# Pwr.net
KiCad netlist of a schematic drawn in Altium Designer
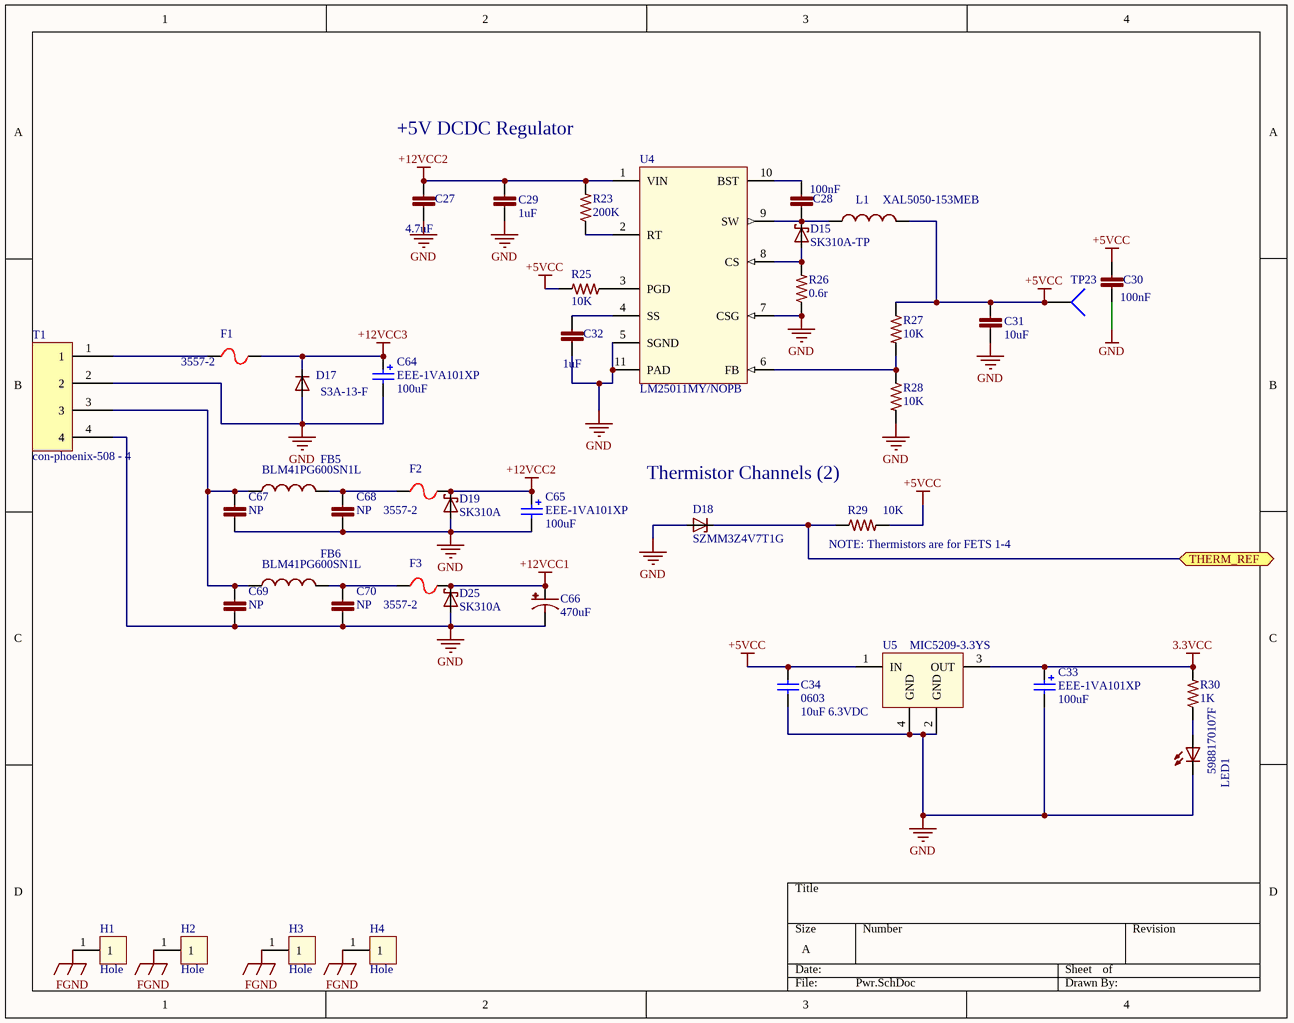
[diagram p0: Pwr.SchDoc]

(export (version "E")
  (design (tool "Eeschema 10.0.6"))
  (components
    (comp (ref "C27")
      (value "4.7uF")
      (footprint "C1206")
      (description "CAP CER 1206 4.7uF 50V 10% X5R")
      (fields
        (field (name "MANUFACTURERPARTNUMBER") "C1206C475K5PACTU")
        (field (name "PUBLISHER") "UltiMachine")
      )
      (libsource (lib "3Delight") (part "C1206C475K5PACTU"))
    )
    (comp (ref "C28")
      (value "100nF")
      (footprint "C0603")
      (description "CAP CER 0603 100nF 50V 10% X7R")
      (fields
        (field (name "MANUFACTURERPARTNUMBER") "C0603C104K5RACTU")
        (field (name "PUBLISHER") "UltiMachine")
      )
      (libsource (lib "3Delight") (part "C0603C104K5RACTU"))
    )
    (comp (ref "C29")
      (value "1uF")
      (footprint "C0805")
      (description "CAP CER 0805 1uF 50V 10% X7R")
      (fields
        (field (name "MANUFACTURERPARTNUMBER") "GRM21BR71H105KA12L")
        (field (name "PUBLISHER") "UltiMachine")
      )
      (libsource (lib "3Delight") (part "GRM21BR71H105KA12L"))
    )
    (comp (ref "C30")
      (value "100nF")
      (footprint "C0603")
      (description "CAP CER 0603 100nF 50V 10% X7R")
      (fields
        (field (name "MANUFACTURERPARTNUMBER") "C0603C104K5RACTU")
        (field (name "PUBLISHER") "UltiMachine")
      )
      (libsource (lib "3Delight") (part "C0603C104K5RACTU"))
    )
    (comp (ref "C31")
      (value "10uF")
      (footprint "C0805")
      (description "CAP CER 0805 10uF 10V 10% X5R")
      (fields
        (field (name "MANUFACTURERPARTNUMBER") "C0805C106K8PACTU")
        (field (name "PUBLISHER") "UltiMachine")
      )
      (libsource (lib "3Delight") (part "C0805C106K8PACTU"))
    )
    (comp (ref "C32")
      (value "1uF")
      (footprint "C0402")
      (description "CAP CER 0402 1uF 6.3V 10% X5R")
      (fields
        (field (name "MANUFACTURERPARTNUMBER") "GRM155R60J105KE19D")
        (field (name "PUBLISHER") "UltiMachine")
      )
      (libsource (lib "3Delight") (part "GRM155R60J105KE19D"))
    )
    (comp (ref "C33")
      (value "EEE-1VA101XP")
      (footprint "EEE-1VA101XP")
      (description "CAP ALUM 100UF 35V 20% SMD")
      (fields (field (name "DIGIKEY PART #") "PCE3951CT-ND") (field (name "ALTIUM_VALUE") "100uF"))
      (libsource (lib "Tigershark3D") (part "EEE-1VA101XP"))
    )
    (comp (ref "C34")
      (value "0603")
      (footprint "C0603")
      (description "CAP CER 10UF 6.3V 10% JB 0603")
      (fields
        (field (name "MFR PART #") "C1608JB0J106K080AB")
        (field (name "MFR") "TDK")
        (field (name "ALTIUM_VALUE") "10uF 6.3VDC")
      )
      (libsource (lib "Tigershark3D") (part "C1608JB0J106K080AB"))
    )
    (comp (ref "C64")
      (value "EEE-1VA101XP")
      (footprint "EEE-1VA101XP")
      (description "CAP ALUM 100UF 35V 20% SMD")
      (fields (field (name "DIGIKEY PART #") "PCE3951CT-ND") (field (name "ALTIUM_VALUE") "100uF"))
      (libsource (lib "Tigershark3D") (part "EEE-1VA101XP"))
    )
    (comp (ref "C65")
      (value "EEE-1VA101XP")
      (footprint "EEE-1VA101XP")
      (description "CAP ALUM 100UF 35V 20% SMD")
      (fields (field (name "DIGIKEY PART #") "PCE3951CT-ND") (field (name "ALTIUM_VALUE") "100uF"))
      (libsource (lib "Tigershark3D") (part "EEE-1VA101XP"))
    )
    (comp (ref "C66")
      (value "470uF")
      (footprint "C12,5-5")
      (description "CAP ALU 470uF 50V 20%")
      (fields
        (field (name "MANUFACTURERPARTNUMBER") "UPW1H471MHD1TO")
        (field (name "PUBLISHER") "UltiMachine")
      )
      (libsource (lib "Tigershark3D") (part "UPW1H471MHD1TO"))
    )
    (comp (ref "C67")
      (value "NP")
      (footprint "C0603")
      (description "CAP CER 0603 100nF 50V 10% X7R")
      (fields
        (field (name "MANUFACTURERPARTNUMBER") "C0603C104K5RACTU")
        (field (name "PUBLISHER") "UltiMachine")
      )
      (libsource (lib "3Delight") (part "C0603C104K5RACTU"))
    )
    (comp (ref "C68")
      (value "NP")
      (footprint "C0603")
      (description "CAP CER 0603 100nF 50V 10% X7R")
      (fields
        (field (name "MANUFACTURERPARTNUMBER") "C0603C104K5RACTU")
        (field (name "PUBLISHER") "UltiMachine")
      )
      (libsource (lib "3Delight") (part "C0603C104K5RACTU"))
    )
    (comp (ref "C69")
      (value "NP")
      (footprint "C0603")
      (description "CAP CER 0603 100nF 50V 10% X7R")
      (fields
        (field (name "MANUFACTURERPARTNUMBER") "C0603C104K5RACTU")
        (field (name "PUBLISHER") "UltiMachine")
      )
      (libsource (lib "3Delight") (part "C0603C104K5RACTU"))
    )
    (comp (ref "C70")
      (value "NP")
      (footprint "C0603")
      (description "CAP CER 0603 100nF 50V 10% X7R")
      (fields
        (field (name "MANUFACTURERPARTNUMBER") "C0603C104K5RACTU")
        (field (name "PUBLISHER") "UltiMachine")
      )
      (libsource (lib "3Delight") (part "C0603C104K5RACTU"))
    )
    (comp (ref "D15")
      (value "SK310A-TP")
      (footprint "SMA-SM")
      (description "DIODE Schottky 3A SMA")
      (fields (field (name "MANUFACTURERPARTNUMBER") "SK310A") (field (name "PUBLISHER") "UltiMachine"))
      (libsource (lib "3Delight") (part "SK310A"))
    )
    (comp (ref "D17")
      (value "S3A-13-F")
      (footprint "DO-214AB")
      (description "DIODE DO-214AB")
      (fields (field (name "PUBLISHER") "UltiMachine"))
      (libsource (lib "3Delight") (part "S3A-13-F"))
    )
    (comp (ref "D18")
      (value "SZMM3Z4V7T1G")
      (footprint "SOD323-R")
      (description "Z-Diode")
      (fields (field (name "MANUFACTURER") "Fairchild") (field (name "PUBLISHER") "UltiMachine"))
      (libsource (lib "Tigershark3D") (part "SZMM3Z4V7T1G"))
    )
    (comp (ref "D19")
      (value "SK310A")
      (footprint "SMA-SM")
      (description "DIODE Schottky 3A SMA")
      (fields (field (name "PUBLISHER") "UltiMachine"))
      (libsource (lib "3Delight") (part "SK310A"))
    )
    (comp (ref "D25")
      (value "SK310A")
      (footprint "SMA-SM")
      (description "DIODE Schottky 3A SMA")
      (fields (field (name "PUBLISHER") "UltiMachine"))
      (libsource (lib "3Delight") (part "SK310A"))
    )
    (comp (ref "F1")
      (value "3557-2")
      (footprint "3557")
      (description "FUSE PTH ATO")
      (fields (field (name "PUBLISHER") "UltiMachine"))
      (libsource (lib "3Delight") (part "3557-2"))
    )
    (comp (ref "F2")
      (value "3557-2")
      (footprint "3557")
      (description "FUSE PTH ATO")
      (fields (field (name "PUBLISHER") "UltiMachine"))
      (libsource (lib "3Delight") (part "3557-2"))
    )
    (comp (ref "F3")
      (value "3557-2")
      (footprint "3557")
      (description "FUSE PTH ATO")
      (fields (field (name "PUBLISHER") "UltiMachine"))
      (libsource (lib "3Delight") (part "3557-2"))
    )
    (comp (ref "FB5")
      (value "BLM41PG600SN1L")
      (footprint "L1806")
      (description "FERRITE BEAD 1806 60ohm")
      (fields (field (name "PUBLISHER") "UltiMachine"))
      (libsource (lib "3Delight") (part "BLM41PG600SN1L"))
    )
    (comp (ref "FB6")
      (value "BLM41PG600SN1L")
      (footprint "L1806")
      (description "FERRITE BEAD 1806 60ohm")
      (fields (field (name "PUBLISHER") "UltiMachine"))
      (libsource (lib "3Delight") (part "BLM41PG600SN1L"))
    )
    (comp (ref "H1")
      (value "Hole")
      (footprint "Wave_hole_3x7-singleSided")
      (libsource (lib "3Delight") (part "Hole"))
    )
    (comp (ref "H2")
      (value "Hole")
      (footprint "Wave_hole_3x7-singleSided")
      (libsource (lib "3Delight") (part "Hole"))
    )
    (comp (ref "H3")
      (value "Hole")
      (footprint "Wave_hole_3x7-singleSided")
      (libsource (lib "3Delight") (part "Hole"))
    )
    (comp (ref "H4")
      (value "Hole")
      (footprint "Wave_hole_3x7-singleSided")
      (libsource (lib "3Delight") (part "Hole"))
    )
    (comp (ref "L1")
      (value "XAL5050-153MEB")
      (footprint "XAL50xx-153")
      (description "IND 15uH 3.9A 20%")
      (fields (field (name "PUBLISHER") "UltiMachine"))
      (libsource (lib "3Delight") (part "XAL5050-153MEB"))
    )
    (comp (ref "LED1")
      (value "5988170107F")
      (footprint "LED2012120")
      (description "LED 0805 Green")
      (fields (field (name "PUBLISHER") "UltiMachine"))
      (libsource (lib "3Delight") (part "5988170107F"))
    )
    (comp (ref "R23")
      (value "200K")
      (footprint "R0402")
      (description "RES 0402 22r 63mW 1%")
      (fields
        (field (name "MANUFACTURERPARTNUMBER") "CRCW0402200KFKED")
        (field (name "PUBLISHER") "UltiMachine")
      )
      (libsource (lib "3Delight") (part "CRCW0402200KFKED"))
    )
    (comp (ref "R25")
      (value "10K")
      (footprint "R0603")
      (description "RES 0603 10K 100mW 1%")
      (fields
        (field (name "MANUFACTURERPARTNUMBER") "ERJ-3EKF1002V")
        (field (name "PUBLISHER") "UltiMachine")
      )
      (libsource (lib "3Delight") (part "ERJ-3EKF1002V"))
    )
    (comp (ref "R26")
      (value "0.6r")
      (footprint "2512R-0.55")
      (description "RES 0.06 OHM 1W 1% 2512 SMD")
      (fields
        (field (name "MANUFACTURERPARTNUMBER") "RL2512FK-070R06L")
        (field (name "PUBLISHER") "UltiMachine")
      )
      (libsource (lib "3Delight") (part "RL2512FK-070R06L"))
    )
    (comp (ref "R27")
      (value "10K")
      (footprint "R0603")
      (description "RES 0603 10K 100mW 1%")
      (fields
        (field (name "MANUFACTURERPARTNUMBER") "ERJ-3EKF1002V")
        (field (name "PUBLISHER") "UltiMachine")
      )
      (libsource (lib "3Delight") (part "ERJ-3EKF1002V"))
    )
    (comp (ref "R28")
      (value "10K")
      (footprint "R0603")
      (description "RES 0603 10K 100mW 1%")
      (fields
        (field (name "MANUFACTURERPARTNUMBER") "ERJ-3EKF1002V")
        (field (name "PUBLISHER") "UltiMachine")
      )
      (libsource (lib "3Delight") (part "ERJ-3EKF1002V"))
    )
    (comp (ref "R29")
      (value "10K")
      (footprint "R0603")
      (description "RES 0603 10K 100mW 1%")
      (fields
        (field (name "MANUFACTURERPARTNUMBER") "ERJ-3EKF1002V")
        (field (name "PUBLISHER") "UltiMachine")
      )
      (libsource (lib "3Delight") (part "ERJ-3EKF1002V"))
    )
    (comp (ref "R30")
      (value "1K")
      (footprint "R0603")
      (description "RES 0603 1K 100mW 1%")
      (fields
        (field (name "MANUFACTURERPARTNUMBER") "ERJ-3EKF1001V")
        (field (name "PUBLISHER") "UltiMachine")
      )
      (libsource (lib "Tigershark3D") (part "ERJ-3EKF1001V"))
    )
    (comp (ref "T1")
      (value "con-phoenix-508 - 4")
      (footprint "MSTBV4")
      (libsource (lib "ZMBo Schematic Library") (part "con-phoenix-508_4"))
    )
    (comp (ref "TP23")
      (value "TP4")
      (footprint "TP-2")
      (description "Socket")
      (fields (field (name "PUBLISHER") "Altium Limited"))
      (libsource (lib "ZMBo Schematic Library") (part "Socket"))
    )
    (comp (ref "U4")
      (value "LM25011MY/NOPB")
      (footprint "VSSOP10")
      (description "REG BUCK")
      (libsource (lib "3Delight") (part "LM25011"))
    )
    (comp (ref "U5")
      (value "MIC5209-3.3YS")
      (footprint "SOT230P700X190-4N")
      (libsource (lib "3Delight") (part "MIC5209-3.3YS"))
    )
  )
  (nets
    (net (code "1") (name "+5VCC") (class "Default")
      (node (ref "C30") (pin "1") (pinfunction "1_1") (pintype "passive"))
      (node (ref "C31") (pin "1") (pinfunction "1_1") (pintype "passive"))
      (node (ref "C34") (pin "2") (pinfunction "2_2") (pintype "passive"))
      (node (ref "L1") (pin "2") (pinfunction "2_2") (pintype "passive"))
      (node (ref "R25") (pin "2") (pinfunction "2_2") (pintype "passive"))
      (node (ref "R27") (pin "1") (pinfunction "1_1") (pintype "passive"))
      (node (ref "R29") (pin "2") (pinfunction "2_2") (pintype "passive"))
      (node (ref "TP23") (pin "1") (pinfunction "1_1") (pintype "passive"))
      (node (ref "U5") (pin "1") (pinfunction "IN_1") (pintype "power_in"))
    )
    (net (code "2") (name "+12VCC1") (class "Default")
      (node (ref "C66") (pin "1") (pinfunction "+_1") (pintype "passive"))
      (node (ref "D25") (pin "C") (pinfunction "C_C") (pintype "passive"))
      (node (ref "F3") (pin "2") (pinfunction "2_2") (pintype "passive"))
    )
    (net (code "3") (name "+12VCC2") (class "Default")
      (node (ref "C27") (pin "1") (pinfunction "1_1") (pintype "passive"))
      (node (ref "C29") (pin "1") (pinfunction "1_1") (pintype "passive"))
      (node (ref "C65") (pin "1") (pinfunction "1_1") (pintype "passive"))
      (node (ref "D19") (pin "C") (pinfunction "C_C") (pintype "passive"))
      (node (ref "F2") (pin "2") (pinfunction "2_2") (pintype "passive"))
      (node (ref "R23") (pin "2") (pinfunction "2_2") (pintype "passive"))
      (node (ref "U4") (pin "1") (pinfunction "VIN_1") (pintype "power_in"))
    )
    (net (code "4") (name "+12VCC3") (class "Default")
      (node (ref "C64") (pin "1") (pinfunction "1_1") (pintype "passive"))
      (node (ref "D17") (pin "C") (pinfunction "C_C") (pintype "passive"))
      (node (ref "F1") (pin "2") (pinfunction "2_2") (pintype "passive"))
    )
    (net (code "5") (name "/THERM_REF") (class "Default")
      (node (ref "D18") (pin "C") (pinfunction "C_C") (pintype "passive"))
      (node (ref "R29") (pin "1") (pinfunction "1_1") (pintype "passive"))
    )
    (net (code "6") (name "3.3VCC") (class "Default")
      (node (ref "C33") (pin "1") (pinfunction "1_1") (pintype "passive"))
      (node (ref "R30") (pin "2") (pinfunction "2_2") (pintype "passive"))
      (node (ref "U5") (pin "3") (pinfunction "OUT_3") (pintype "power_in"))
    )
    (net (code "7") (name "FGND") (class "Default")
      (node (ref "H1") (pin "1") (pinfunction "1_1") (pintype "power_in"))
      (node (ref "H2") (pin "1") (pinfunction "1_1") (pintype "power_in"))
      (node (ref "H3") (pin "1") (pinfunction "1_1") (pintype "power_in"))
      (node (ref "H4") (pin "1") (pinfunction "1_1") (pintype "power_in"))
    )
    (net (code "8") (name "GND") (class "Default")
      (node (ref "C27") (pin "2") (pinfunction "2_2") (pintype "passive"))
      (node (ref "C29") (pin "2") (pinfunction "2_2") (pintype "passive"))
      (node (ref "C30") (pin "2") (pinfunction "2_2") (pintype "passive"))
      (node (ref "C31") (pin "2") (pinfunction "2_2") (pintype "passive"))
      (node (ref "C32") (pin "2") (pinfunction "2_2") (pintype "passive"))
      (node (ref "C33") (pin "2") (pinfunction "2_2") (pintype "passive"))
      (node (ref "C34") (pin "1") (pinfunction "1_1") (pintype "passive"))
      (node (ref "C64") (pin "2") (pinfunction "2_2") (pintype "passive"))
      (node (ref "C65") (pin "2") (pinfunction "2_2") (pintype "passive"))
      (node (ref "C66") (pin "2") (pinfunction "-_2") (pintype "passive"))
      (node (ref "C67") (pin "2") (pinfunction "2_2") (pintype "passive"))
      (node (ref "C68") (pin "2") (pinfunction "2_2") (pintype "passive"))
      (node (ref "C69") (pin "2") (pinfunction "2_2") (pintype "passive"))
      (node (ref "C70") (pin "2") (pinfunction "2_2") (pintype "passive"))
      (node (ref "D17") (pin "A") (pinfunction "A_A") (pintype "passive"))
      (node (ref "D18") (pin "A") (pinfunction "A_A") (pintype "passive"))
      (node (ref "D19") (pin "A") (pinfunction "A_A") (pintype "passive"))
      (node (ref "D25") (pin "A") (pinfunction "A_A") (pintype "passive"))
      (node (ref "LED1") (pin "C") (pinfunction "C_C") (pintype "passive"))
      (node (ref "R26") (pin "1") (pinfunction "1_1") (pintype "passive"))
      (node (ref "R28") (pin "2") (pinfunction "2_2") (pintype "passive"))
      (node (ref "T1") (pin "2") (pinfunction "2_2") (pintype "passive"))
      (node (ref "T1") (pin "4") (pinfunction "4_4") (pintype "passive"))
      (node (ref "U4") (pin "11") (pinfunction "PAD_11") (pintype "power_in"))
      (node (ref "U4") (pin "5") (pinfunction "SGND_5") (pintype "power_in"))
      (node (ref "U4") (pin "7") (pinfunction "CSG_7") (pintype "input"))
      (node (ref "U5") (pin "2") (pinfunction "GND_2") (pintype "power_in"))
      (node (ref "U5") (pin "4") (pinfunction "GND_4") (pintype "power_in"))
    )
    (net (code "9") (name "Net-(C67-Pad1)") (class "Default")
      (node (ref "C67") (pin "1") (pinfunction "1_1") (pintype "passive"))
      (node (ref "C69") (pin "1") (pinfunction "1_1") (pintype "passive"))
      (node (ref "FB5") (pin "1") (pinfunction "1_1") (pintype "passive"))
      (node (ref "FB6") (pin "1") (pinfunction "1_1") (pintype "passive"))
      (node (ref "T1") (pin "3") (pinfunction "3_3") (pintype "passive"))
    )
    (net (code "10") (name "Net-(C68-Pad1)") (class "Default")
      (node (ref "C68") (pin "1") (pinfunction "1_1") (pintype "passive"))
      (node (ref "F2") (pin "1") (pinfunction "1_1") (pintype "passive"))
      (node (ref "FB5") (pin "2") (pinfunction "2_2") (pintype "passive"))
    )
    (net (code "11") (name "Net-(C70-Pad1)") (class "Default")
      (node (ref "C70") (pin "1") (pinfunction "1_1") (pintype "passive"))
      (node (ref "F3") (pin "1") (pinfunction "1_1") (pintype "passive"))
      (node (ref "FB6") (pin "2") (pinfunction "2_2") (pintype "passive"))
    )
    (net (code "12") (name "Net-(F1-Pad1)") (class "Default")
      (node (ref "F1") (pin "1") (pinfunction "1_1") (pintype "passive"))
      (node (ref "T1") (pin "1") (pinfunction "1_1") (pintype "passive"))
    )
    (net (code "13") (name "Net-(LED1-PadA)") (class "Default")
      (node (ref "LED1") (pin "A") (pinfunction "A_A") (pintype "passive"))
      (node (ref "R30") (pin "1") (pinfunction "1_1") (pintype "passive"))
    )
    (net (code "14") (name "Net-(U4-BST)") (class "Default")
      (node (ref "C28") (pin "1") (pinfunction "1_1") (pintype "passive"))
      (node (ref "U4") (pin "10") (pinfunction "BST_10") (pintype "power_in"))
    )
    (net (code "15") (name "Net-(U4-CS)") (class "Default")
      (node (ref "D15") (pin "A") (pinfunction "A_A") (pintype "passive"))
      (node (ref "R26") (pin "2") (pinfunction "2_2") (pintype "passive"))
      (node (ref "U4") (pin "8") (pinfunction "CS_8") (pintype "input"))
    )
    (net (code "16") (name "Net-(U4-FB)") (class "Default")
      (node (ref "R27") (pin "2") (pinfunction "2_2") (pintype "passive"))
      (node (ref "R28") (pin "1") (pinfunction "1_1") (pintype "passive"))
      (node (ref "U4") (pin "6") (pinfunction "FB_6") (pintype "input"))
    )
    (net (code "17") (name "Net-(U4-PGD)") (class "Default")
      (node (ref "R25") (pin "1") (pinfunction "1_1") (pintype "passive"))
      (node (ref "U4") (pin "3") (pinfunction "PGD_3") (pintype "power_in"))
    )
    (net (code "18") (name "Net-(U4-RT)") (class "Default")
      (node (ref "R23") (pin "1") (pinfunction "1_1") (pintype "passive"))
      (node (ref "U4") (pin "2") (pinfunction "RT_2") (pintype "power_in"))
    )
    (net (code "19") (name "Net-(U4-SS)") (class "Default")
      (node (ref "C32") (pin "1") (pinfunction "1_1") (pintype "passive"))
      (node (ref "U4") (pin "4") (pinfunction "SS_4") (pintype "power_in"))
    )
    (net (code "20") (name "Net-(U4-SW)") (class "Default")
      (node (ref "C28") (pin "2") (pinfunction "2_2") (pintype "passive"))
      (node (ref "D15") (pin "C") (pinfunction "C_C") (pintype "passive"))
      (node (ref "L1") (pin "1") (pinfunction "1_1") (pintype "passive"))
      (node (ref "U4") (pin "9") (pinfunction "SW_9") (pintype "output"))
    )
  )
)
